# Port.net
KiCad netlist of a schematic drawn in Altium Designer
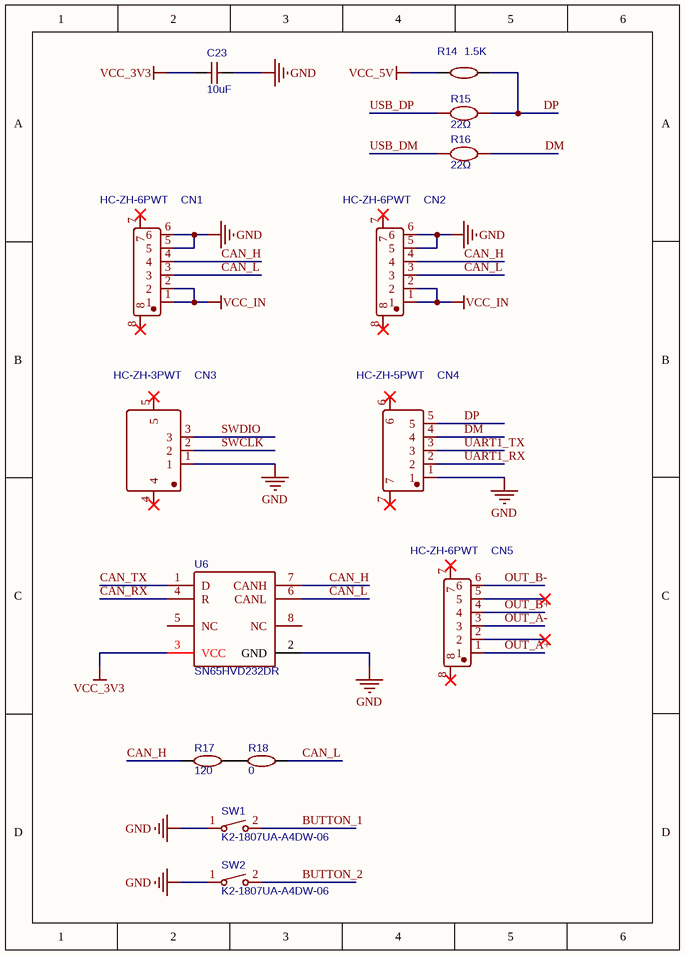
[diagram p0: Port.SchDoc]

(export (version "E")
  (design (tool "Eeschema 10.0.6"))
  (components
    (comp (ref "C23")
      (value "10uF")
      (footprint "C1206")
      (fields
        (field (name "BOM_MANUFACTURER PART") "CL31A106KBHNNNE")
        (field (name "BOM_SUPPLIER PART") "C13585")
      )
      (libsource (lib "10uF") (part "10uF"))
    )
    (comp (ref "CN1")
      (value "HC-ZH-6PWT")
      (footprint "CONN-SMD_6P-P1.50_HCTL_HC-ZH-6PWT")
      (fields (field (name "BOM_SUPPLIER PART") "C2845428") (field (name "CONTRIBUTOR") "LCSC"))
      (libsource (lib "6P 1.5mm") (part "HC-ZH-6PWT"))
    )
    (comp (ref "CN2")
      (value "HC-ZH-6PWT")
      (footprint "CONN-SMD_6P-P1.50_HCTL_HC-ZH-6PWT")
      (fields (field (name "BOM_SUPPLIER PART") "C2845428") (field (name "CONTRIBUTOR") "LCSC"))
      (libsource (lib "6P 1.5mm") (part "HC-ZH-6PWT"))
    )
    (comp (ref "CN3")
      (value "HC-ZH-3PWT")
      (footprint "CONN-SMD_HC-ZH-3PWT")
      (fields (field (name "BOM_SUPPLIER PART") "C2845425") (field (name "CONTRIBUTOR") "LCSC"))
      (libsource (lib "3P 1.5mm") (part "HC-ZH-3PWT"))
    )
    (comp (ref "CN4")
      (value "HC-ZH-5PWT")
      (footprint "CONN-SMD_5P-P1.50_HCTL_HC-ZH-5PWT")
      (fields (field (name "BOM_SUPPLIER PART") "C2845427") (field (name "CONTRIBUTOR") "LCSC"))
      (libsource (lib "5P 1.5mm") (part "HC-ZH-5PWT"))
    )
    (comp (ref "CN5")
      (value "HC-ZH-6PWT")
      (footprint "CONN-SMD_6P-P1.50_HCTL_HC-ZH-6PWT")
      (fields (field (name "BOM_SUPPLIER PART") "C2845428") (field (name "CONTRIBUTOR") "LCSC"))
      (libsource (lib "6P 1.5mm") (part "HC-ZH-6PWT"))
    )
    (comp (ref "R14")
      (value "1.5K")
      (footprint "R0603")
      (fields
        (field (name "BOM_MANUFACTURER PART") "0603WAF1501T5E")
        (field (name "BOM_SUPPLIER PART") "C22843")
      )
      (libsource (lib "1.5K") (part "1.5K"))
    )
    (comp (ref "R15")
      (value "22Ω")
      (footprint "R0805")
      (fields
        (field (name "BOM_SUPPLIER PART") "C441970")
        (field (name "BOM_MANUFACTURER PART") "ERJP06F22R0V")
        (field (name "CONTRIBUTOR") "LCSC")
      )
      (libsource (lib "22R") (part "22Ω"))
    )
    (comp (ref "R16")
      (value "22Ω")
      (footprint "R0805")
      (fields
        (field (name "BOM_SUPPLIER PART") "C441970")
        (field (name "BOM_MANUFACTURER PART") "ERJP06F22R0V")
        (field (name "CONTRIBUTOR") "LCSC")
      )
      (libsource (lib "22R") (part "22Ω"))
    )
    (comp (ref "R17")
      (value "120")
      (footprint "R0603")
      (fields
        (field (name "BOM_MANUFACTURER PART") "0603WAF1200T5E")
        (field (name "BOM_SUPPLIER PART") "C22787")
      )
      (libsource (lib "120R") (part "120"))
    )
    (comp (ref "R18")
      (value "0")
      (footprint "R0805")
      (fields
        (field (name "BOM_MANUFACTURER PART") "WR08X000PTL")
        (field (name "BOM_SUPPLIER PART") "C112378")
      )
      (libsource (lib "JUMP LINE") (part "0"))
    )
    (comp (ref "SW1")
      (value "K2-1807UA-A4DW-06")
      (footprint "KEY-SMD_L4.0-W2.9-L")
      (fields (field (name "BOM_SUPPLIER PART") "C502307") (field (name "CONTRIBUTOR") "LCSC"))
      (libsource (lib "BUTTON") (part "K2-1807UA-A4DW-06"))
    )
    (comp (ref "SW2")
      (value "K2-1807UA-A4DW-06")
      (footprint "KEY-SMD_L4.0-W2.9-L")
      (fields (field (name "BOM_SUPPLIER PART") "C502307") (field (name "CONTRIBUTOR") "LCSC"))
      (libsource (lib "BUTTON") (part "K2-1807UA-A4DW-06"))
    )
    (comp (ref "U6")
      (value "SN65HVD232DR")
      (footprint "SOIC-8_L5.0-W4.0-P1.27-LS6.0-BL")
      (fields (field (name "BOM_SUPPLIER PART") "C30530"))
      (libsource (lib "SN65HVD232DR") (part "SN65HVD232DR"))
    )
  )
  (nets
    (net (code "1") (name "/BUTTON_1") (class "Default")
      (node (ref "SW1") (pin "2") (pinfunction "2_2") (pintype "passive"))
    )
    (net (code "2") (name "/BUTTON_2") (class "Default")
      (node (ref "SW2") (pin "2") (pinfunction "2_2") (pintype "passive"))
    )
    (net (code "3") (name "/CAN_H") (class "Default")
      (node (ref "CN1") (pin "4") (pinfunction "4_4") (pintype "passive"))
      (node (ref "CN2") (pin "4") (pinfunction "4_4") (pintype "passive"))
      (node (ref "R17") (pin "1") (pinfunction "1_1") (pintype "passive"))
      (node (ref "U6") (pin "7") (pinfunction "CANH_7") (pintype "passive"))
    )
    (net (code "4") (name "/CAN_L") (class "Default")
      (node (ref "CN1") (pin "3") (pinfunction "3_3") (pintype "passive"))
      (node (ref "CN2") (pin "3") (pinfunction "3_3") (pintype "passive"))
      (node (ref "R18") (pin "2") (pinfunction "2_2") (pintype "passive"))
      (node (ref "U6") (pin "6") (pinfunction "CANL_6") (pintype "passive"))
    )
    (net (code "5") (name "/CAN_RX") (class "Default")
      (node (ref "U6") (pin "4") (pinfunction "R_4") (pintype "passive"))
    )
    (net (code "6") (name "/CAN_TX") (class "Default")
      (node (ref "U6") (pin "1") (pinfunction "D_1") (pintype "passive"))
    )
    (net (code "7") (name "/DM") (class "Default")
      (node (ref "CN4") (pin "4") (pinfunction "4_4") (pintype "passive"))
      (node (ref "R16") (pin "2") (pinfunction "2_2") (pintype "passive"))
    )
    (net (code "8") (name "/DP") (class "Default")
      (node (ref "CN4") (pin "5") (pinfunction "5_5") (pintype "passive"))
      (node (ref "R14") (pin "2") (pinfunction "2_2") (pintype "passive"))
      (node (ref "R15") (pin "2") (pinfunction "2_2") (pintype "passive"))
    )
    (net (code "9") (name "/OUT_A+") (class "Default")
      (node (ref "CN5") (pin "1") (pinfunction "1_1") (pintype "passive"))
    )
    (net (code "10") (name "/OUT_A-") (class "Default")
      (node (ref "CN5") (pin "3") (pinfunction "3_3") (pintype "passive"))
    )
    (net (code "11") (name "/OUT_B+") (class "Default")
      (node (ref "CN5") (pin "4") (pinfunction "4_4") (pintype "passive"))
    )
    (net (code "12") (name "/OUT_B-") (class "Default")
      (node (ref "CN5") (pin "6") (pinfunction "6_6") (pintype "passive"))
    )
    (net (code "13") (name "/SWCLK") (class "Default")
      (node (ref "CN3") (pin "2") (pinfunction "2_2") (pintype "passive"))
    )
    (net (code "14") (name "/SWDIO") (class "Default")
      (node (ref "CN3") (pin "3") (pinfunction "3_3") (pintype "passive"))
    )
    (net (code "15") (name "/UART1_RX") (class "Default")
      (node (ref "CN4") (pin "2") (pinfunction "2_2") (pintype "passive"))
    )
    (net (code "16") (name "/UART1_TX") (class "Default")
      (node (ref "CN4") (pin "3") (pinfunction "3_3") (pintype "passive"))
    )
    (net (code "17") (name "/USB_DM") (class "Default")
      (node (ref "R16") (pin "1") (pinfunction "1_1") (pintype "passive"))
    )
    (net (code "18") (name "/USB_DP") (class "Default")
      (node (ref "R15") (pin "1") (pinfunction "1_1") (pintype "passive"))
    )
    (net (code "19") (name "GND") (class "Default")
      (node (ref "C23") (pin "2") (pinfunction "2_2") (pintype "passive"))
      (node (ref "CN1") (pin "5") (pinfunction "5_5") (pintype "passive"))
      (node (ref "CN1") (pin "6") (pinfunction "6_6") (pintype "passive"))
      (node (ref "CN2") (pin "5") (pinfunction "5_5") (pintype "passive"))
      (node (ref "CN2") (pin "6") (pinfunction "6_6") (pintype "passive"))
      (node (ref "CN3") (pin "1") (pinfunction "1_1") (pintype "passive"))
      (node (ref "CN4") (pin "1") (pinfunction "1_1") (pintype "passive"))
      (node (ref "SW1") (pin "1") (pinfunction "1_1") (pintype "passive"))
      (node (ref "SW2") (pin "1") (pinfunction "1_1") (pintype "passive"))
      (node (ref "U6") (pin "2") (pinfunction "GND_2") (pintype "passive"))
    )
    (net (code "20") (name "Net-(R17-Pad2)") (class "Default")
      (node (ref "R17") (pin "2") (pinfunction "2_2") (pintype "passive"))
      (node (ref "R18") (pin "1") (pinfunction "1_1") (pintype "passive"))
    )
    (net (code "21") (name "VCC_3V3") (class "Default")
      (node (ref "C23") (pin "1") (pinfunction "1_1") (pintype "passive"))
      (node (ref "U6") (pin "3") (pinfunction "VCC_3") (pintype "passive"))
    )
    (net (code "22") (name "VCC_5V") (class "Default")
      (node (ref "R14") (pin "1") (pinfunction "1_1") (pintype "passive"))
    )
    (net (code "23") (name "VCC_IN") (class "Default")
      (node (ref "CN1") (pin "1") (pinfunction "1_1") (pintype "passive"))
      (node (ref "CN1") (pin "2") (pinfunction "2_2") (pintype "passive"))
      (node (ref "CN2") (pin "1") (pinfunction "1_1") (pintype "passive"))
      (node (ref "CN2") (pin "2") (pinfunction "2_2") (pintype "passive"))
    )
    (net (code "24") (name "unconnected-(CN1-Pad7)") (class "Default")
      (node (ref "CN1") (pin "7") (pinfunction "7_7") (pintype "passive+no_connect"))
    )
    (net (code "25") (name "unconnected-(CN1-Pad8)") (class "Default")
      (node (ref "CN1") (pin "8") (pinfunction "8_8") (pintype "passive+no_connect"))
    )
    (net (code "26") (name "unconnected-(CN2-Pad7)") (class "Default")
      (node (ref "CN2") (pin "7") (pinfunction "7_7") (pintype "passive+no_connect"))
    )
    (net (code "27") (name "unconnected-(CN2-Pad8)") (class "Default")
      (node (ref "CN2") (pin "8") (pinfunction "8_8") (pintype "passive+no_connect"))
    )
    (net (code "28") (name "unconnected-(CN3-Pad4)") (class "Default")
      (node (ref "CN3") (pin "4") (pinfunction "4_4") (pintype "passive+no_connect"))
    )
    (net (code "29") (name "unconnected-(CN3-Pad5)") (class "Default")
      (node (ref "CN3") (pin "5") (pinfunction "5_5") (pintype "passive+no_connect"))
    )
    (net (code "30") (name "unconnected-(CN4-Pad6)") (class "Default")
      (node (ref "CN4") (pin "6") (pinfunction "6_6") (pintype "passive+no_connect"))
    )
    (net (code "31") (name "unconnected-(CN4-Pad7)") (class "Default")
      (node (ref "CN4") (pin "7") (pinfunction "7_7") (pintype "passive+no_connect"))
    )
    (net (code "32") (name "unconnected-(CN5-Pad2)") (class "Default")
      (node (ref "CN5") (pin "2") (pinfunction "2_2") (pintype "passive+no_connect"))
    )
    (net (code "33") (name "unconnected-(CN5-Pad5)") (class "Default")
      (node (ref "CN5") (pin "5") (pinfunction "5_5") (pintype "passive+no_connect"))
    )
    (net (code "34") (name "unconnected-(CN5-Pad7)") (class "Default")
      (node (ref "CN5") (pin "7") (pinfunction "7_7") (pintype "passive+no_connect"))
    )
    (net (code "35") (name "unconnected-(CN5-Pad8)") (class "Default")
      (node (ref "CN5") (pin "8") (pinfunction "8_8") (pintype "passive+no_connect"))
    )
    (net (code "36") (name "unconnected-(U6-NC-Pad5)") (class "Default")
      (node (ref "U6") (pin "5") (pinfunction "NC_5") (pintype "passive"))
    )
    (net (code "37") (name "unconnected-(U6-NC-Pad8)") (class "Default")
      (node (ref "U6") (pin "8") (pinfunction "NC_8") (pintype "passive"))
    )
  )
)
